# Mini-WaveGen.net
KiCad netlist of a schematic drawn in Altium Designer
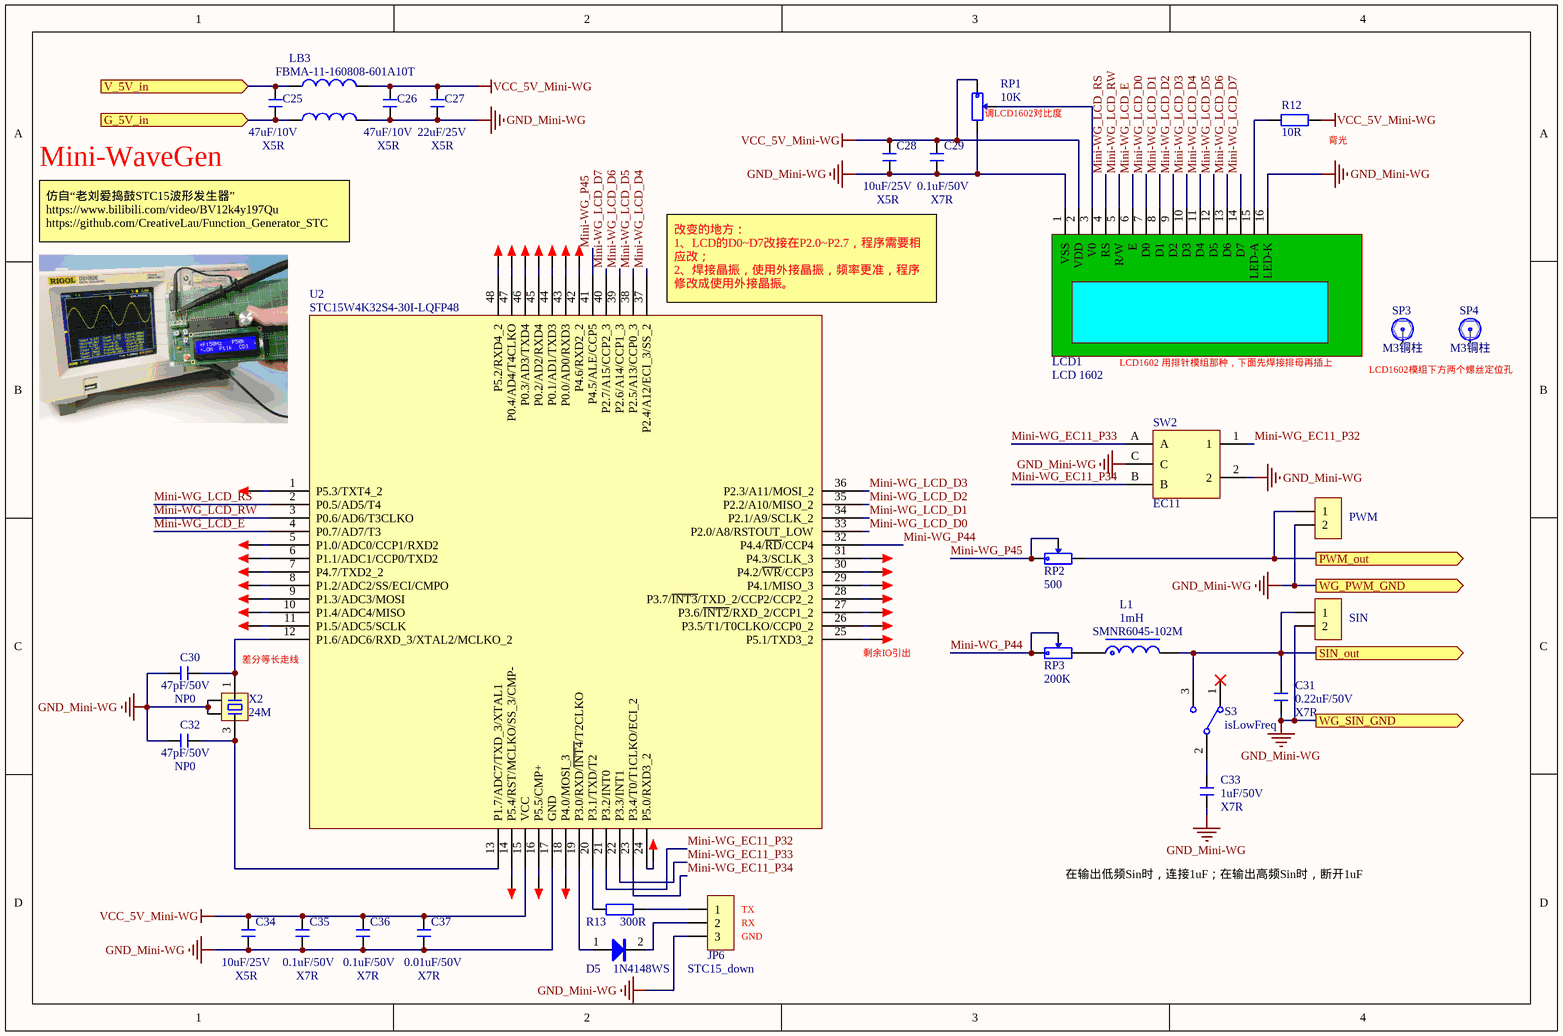
[diagram p0: Mini-WaveGen.SchDoc]

(export (version "E")
  (design (tool "Eeschema 10.0.6"))
  (components
    (comp (ref "C25")
      (value "47uF/10V")
      (footprint "C 1206_L")
      (description "无极性贴片电容 X5R")
      (fields (field (name "BOM名称") "X5R"))
      (libsource (lib "Foundation_temp") (part "C X5R"))
    )
    (comp (ref "C26")
      (value "47uF/10V")
      (footprint "C 1206_L")
      (description "无极性贴片电容 X5R")
      (fields (field (name "BOM名称") "X5R"))
      (libsource (lib "Foundation_temp") (part "C X5R"))
    )
    (comp (ref "C27")
      (value "22uF/25V")
      (footprint "C 0805_L")
      (description "无极性贴片电容 X5R")
      (fields (field (name "BOM名称") "X5R"))
      (libsource (lib "Foundation_temp") (part "C X5R"))
    )
    (comp (ref "C28")
      (value "10uF/25V")
      (footprint "C 0603_L")
      (description "无极性贴片电容 X5R")
      (fields (field (name "BOM名称") "X5R"))
      (libsource (lib "Foundation_temp") (part "C X5R"))
    )
    (comp (ref "C29")
      (value "0.1uF/50V")
      (footprint "C 0402_L")
      (description "无极性贴片电容 X7R")
      (fields (field (name "BOM名称") "X7R"))
      (libsource (lib "Foundation_temp") (part "C X7R"))
    )
    (comp (ref "C30")
      (value "47pF/50V")
      (footprint "C 0402_L")
      (description "无极性贴片电容 NP0")
      (fields (field (name "BOM名称") "NP0"))
      (libsource (lib "Foundation_temp") (part "C NP0"))
    )
    (comp (ref "C31")
      (value "0.22uF/50V")
      (footprint "C 0603_L")
      (description "无极性贴片电容 X7R")
      (fields (field (name "BOM名称") "X7R"))
      (libsource (lib "Foundation_temp") (part "C X7R"))
    )
    (comp (ref "C32")
      (value "47pF/50V")
      (footprint "C 0402_L")
      (description "无极性贴片电容 NP0")
      (fields (field (name "BOM名称") "NP0"))
      (libsource (lib "Foundation_temp") (part "C NP0"))
    )
    (comp (ref "C33")
      (value "1uF/50V")
      (footprint "C 0603_L")
      (description "无极性贴片电容 X7R")
      (fields (field (name "BOM名称") "X7R"))
      (libsource (lib "Foundation_temp") (part "C X7R"))
    )
    (comp (ref "C34")
      (value "10uF/25V")
      (footprint "C 0603_L")
      (description "无极性贴片电容 X5R")
      (fields (field (name "BOM名称") "X5R"))
      (libsource (lib "Foundation_temp") (part "C X5R"))
    )
    (comp (ref "C35")
      (value "0.1uF/50V")
      (footprint "C 0402_L")
      (description "无极性贴片电容 X7R")
      (fields (field (name "BOM名称") "X7R"))
      (libsource (lib "Foundation_temp") (part "C X7R"))
    )
    (comp (ref "C36")
      (value "0.1uF/50V")
      (footprint "C 0402_L")
      (description "无极性贴片电容 X7R")
      (fields (field (name "BOM名称") "X7R"))
      (libsource (lib "Foundation_temp") (part "C X7R"))
    )
    (comp (ref "C37")
      (value "0.01uF/50V")
      (footprint "C 0402_L")
      (description "无极性贴片电容 X7R")
      (fields (field (name "BOM名称") "X7R"))
      (libsource (lib "Foundation_temp") (part "C X7R"))
    )
    (comp (ref "D5")
      (value "1N4148WS")
      (footprint "SOD-323")
      (description "高速开关二极管")
      (fields (field (name "版权归属") "源创客"))
      (libsource (lib "8.1   - 二极管-整流桥") (part "1N4148"))
    )
    (comp (ref "JP4")
      (value "PWM")
      (footprint "HDR2.54-WS-2P")
      (description "2P接插件")
      (fields (field (name "版权归属") "源创客"))
      (libsource (lib "4.6   - 接插件-脚距2.54") (part "Header 2"))
    )
    (comp (ref "JP5")
      (value "SIN")
      (footprint "HDR2.54-WS-2P")
      (description "2P接插件")
      (fields (field (name "版权归属") "源创客"))
      (libsource (lib "4.6   - 接插件-脚距2.54") (part "Header 2"))
    )
    (comp (ref "JP6")
      (value "STC15_down")
      (footprint "HDR2.54-WS-3P")
      (description "3P接插件")
      (fields (field (name "版权归属") "源创客"))
      (libsource (lib "4.6   - 接插件-脚距2.54") (part "Header 3"))
    )
    (comp (ref "L1")
      (value "1mH")
      (footprint "NR6045")
      (description "SMNR6045-102M")
      (fields (field (name "BOM名称") "SMNR6045-102M") (field (name "版权归属") "源创客"))
      (libsource (lib "3.1   - 电阻-电容-电感") (part "L-NR"))
    )
    (comp (ref "LB3")
      (value "FBMA-11-160808-601A10T")
      (footprint "FB 0603_L")
      (description "磁珠 600R@100MHz")
      (fields (field (name "版权归属") "源创客"))
      (libsource (lib "3.1   - 电阻-电容-电感") (part "LB"))
    )
    (comp (ref "LB4")
      (value "FBMA-11-160808-601A10T")
      (footprint "FB 0603_L")
      (description "磁珠 600R@100MHz")
      (fields (field (name "版权归属") "源创客"))
      (libsource (lib "3.1   - 电阻-电容-电感") (part "LB"))
    )
    (comp (ref "LCD1")
      (value "LCD 1602")
      (footprint "LCD-1602")
      (fields (field (name "版权归属") "源创客"))
      (libsource (lib "9.2   - 显示器件") (part "LCD 1602"))
    )
    (comp (ref "R12")
      (value "10R")
      (footprint "R 0805_L")
      (description "贴片电阻 E-96 1%")
      (libsource (lib "Foundation_temp") (part "R"))
    )
    (comp (ref "R13")
      (value "300R")
      (footprint "R 0402_L")
      (description "贴片电阻 E-96 1%")
      (libsource (lib "Foundation_temp") (part "R"))
    )
    (comp (ref "RP1")
      (value "10K")
      (footprint "3362P")
      (description "插件单联电位器")
      (fields (field (name "版权归属") "源创客"))
      (libsource (lib "3.1   - 电阻-电容-电感") (part "RP-ID"))
    )
    (comp (ref "RP2")
      (value "500")
      (footprint "3362P")
      (description "插件单联电位器")
      (fields (field (name "版权归属") "源创客"))
      (libsource (lib "3.1   - 电阻-电容-电感") (part "RP-ID"))
    )
    (comp (ref "RP3")
      (value "200K")
      (footprint "3362P")
      (description "插件单联电位器")
      (fields (field (name "版权归属") "源创客"))
      (libsource (lib "3.1   - 电阻-电容-电感") (part "RP-ID"))
    )
    (comp (ref "S3")
      (value "isLowFreq")
      (footprint "MSK-12C01-07")
      (description "1路拨动开关")
      (fields (field (name "版权归属") "源创客"))
      (libsource (lib "5.1   - 按键-开关") (part "SSW-1P"))
    )
    (comp (ref "SP3")
      (value "M3铜柱")
      (footprint "M3x4_L")
      (description "铜柱")
      (fields (field (name "版权归属") "源创客"))
      (libsource (lib "15.1 - 未分类器件") (part "铜柱小焊盘"))
    )
    (comp (ref "SP4")
      (value "M3铜柱")
      (footprint "M3x4_L")
      (description "铜柱")
      (fields (field (name "版权归属") "源创客"))
      (libsource (lib "15.1 - 未分类器件") (part "铜柱小焊盘"))
    )
    (comp (ref "SW2")
      (value "EC11")
      (footprint "EC11-B")
      (description "数字开关编码器")
      (fields (field (name "版权归属") "源创客"))
      (libsource (lib "5.1   - 按键-开关") (part "EC11"))
    )
    (comp (ref "TP4")
      (value "IO")
      (footprint "TEST 1")
      (description "测试点")
      (fields (field (name "版权归属") "源创客"))
      (libsource (lib "15.1 - 未分类器件") (part "TEST"))
    )
    (comp (ref "TP5")
      (value "IO")
      (footprint "TEST 1")
      (description "测试点")
      (fields (field (name "版权归属") "源创客"))
      (libsource (lib "15.1 - 未分类器件") (part "TEST"))
    )
    (comp (ref "TP6")
      (value "IO")
      (footprint "TEST 1")
      (description "测试点")
      (fields (field (name "版权归属") "源创客"))
      (libsource (lib "15.1 - 未分类器件") (part "TEST"))
    )
    (comp (ref "TP7")
      (value "IO")
      (footprint "TEST 1")
      (description "测试点")
      (fields (field (name "版权归属") "源创客"))
      (libsource (lib "15.1 - 未分类器件") (part "TEST"))
    )
    (comp (ref "TP8")
      (value "IO")
      (footprint "TEST 1")
      (description "测试点")
      (fields (field (name "版权归属") "源创客"))
      (libsource (lib "15.1 - 未分类器件") (part "TEST"))
    )
    (comp (ref "TP9")
      (value "IO")
      (footprint "TEST 1")
      (description "测试点")
      (fields (field (name "版权归属") "源创客"))
      (libsource (lib "15.1 - 未分类器件") (part "TEST"))
    )
    (comp (ref "TP10")
      (value "IO")
      (footprint "TEST 1")
      (description "测试点")
      (fields (field (name "版权归属") "源创客"))
      (libsource (lib "15.1 - 未分类器件") (part "TEST"))
    )
    (comp (ref "TP11")
      (value "IO")
      (footprint "TEST 1")
      (description "测试点")
      (fields (field (name "版权归属") "源创客"))
      (libsource (lib "15.1 - 未分类器件") (part "TEST"))
    )
    (comp (ref "TP12")
      (value "IO")
      (footprint "TEST 1")
      (description "测试点")
      (fields (field (name "版权归属") "源创客"))
      (libsource (lib "15.1 - 未分类器件") (part "TEST"))
    )
    (comp (ref "TP13")
      (value "IO")
      (footprint "TEST 1")
      (description "测试点")
      (fields (field (name "版权归属") "源创客"))
      (libsource (lib "15.1 - 未分类器件") (part "TEST"))
    )
    (comp (ref "TP14")
      (value "IO")
      (footprint "TEST 1")
      (description "测试点")
      (fields (field (name "版权归属") "源创客"))
      (libsource (lib "15.1 - 未分类器件") (part "TEST"))
    )
    (comp (ref "TP15")
      (value "IO")
      (footprint "TEST 1")
      (description "测试点")
      (fields (field (name "版权归属") "源创客"))
      (libsource (lib "15.1 - 未分类器件") (part "TEST"))
    )
    (comp (ref "TP16")
      (value "IO")
      (footprint "TEST 1")
      (description "测试点")
      (fields (field (name "版权归属") "源创客"))
      (libsource (lib "15.1 - 未分类器件") (part "TEST"))
    )
    (comp (ref "TP17")
      (value "IO")
      (footprint "TEST 1")
      (description "测试点")
      (fields (field (name "版权归属") "源创客"))
      (libsource (lib "15.1 - 未分类器件") (part "TEST"))
    )
    (comp (ref "TP18")
      (value "IO")
      (footprint "TEST 1")
      (description "测试点")
      (fields (field (name "版权归属") "源创客"))
      (libsource (lib "15.1 - 未分类器件") (part "TEST"))
    )
    (comp (ref "TP19")
      (value "IO")
      (footprint "TEST 1")
      (description "测试点")
      (fields (field (name "版权归属") "源创客"))
      (libsource (lib "15.1 - 未分类器件") (part "TEST"))
    )
    (comp (ref "TP20")
      (value "IO")
      (footprint "TEST 1")
      (description "测试点")
      (fields (field (name "版权归属") "源创客"))
      (libsource (lib "15.1 - 未分类器件") (part "TEST"))
    )
    (comp (ref "TP21")
      (value "IO")
      (footprint "TEST 1")
      (description "测试点")
      (fields (field (name "版权归属") "源创客"))
      (libsource (lib "15.1 - 未分类器件") (part "TEST"))
    )
    (comp (ref "TP22")
      (value "IO")
      (footprint "TEST 1")
      (description "测试点")
      (fields (field (name "版权归属") "源创客"))
      (libsource (lib "15.1 - 未分类器件") (part "TEST"))
    )
    (comp (ref "TP23")
      (value "IO")
      (footprint "TEST 1")
      (description "测试点")
      (fields (field (name "版权归属") "源创客"))
      (libsource (lib "15.1 - 未分类器件") (part "TEST"))
    )
    (comp (ref "TP24")
      (value "IO")
      (footprint "TEST 1")
      (description "测试点")
      (fields (field (name "版权归属") "源创客"))
      (libsource (lib "15.1 - 未分类器件") (part "TEST"))
    )
    (comp (ref "TP25")
      (value "IO")
      (footprint "TEST 1")
      (description "测试点")
      (fields (field (name "版权归属") "源创客"))
      (libsource (lib "15.1 - 未分类器件") (part "TEST"))
    )
    (comp (ref "TP26")
      (value "IO")
      (footprint "TEST 1")
      (description "测试点")
      (fields (field (name "版权归属") "源创客"))
      (libsource (lib "15.1 - 未分类器件") (part "TEST"))
    )
    (comp (ref "TP27")
      (value "IO")
      (footprint "TEST 1")
      (description "测试点")
      (fields (field (name "版权归属") "源创客"))
      (libsource (lib "15.1 - 未分类器件") (part "TEST"))
    )
    (comp (ref "TP28")
      (value "IO")
      (footprint "TEST 1")
      (description "测试点")
      (fields (field (name "版权归属") "源创客"))
      (libsource (lib "15.1 - 未分类器件") (part "TEST"))
    )
    (comp (ref "TP29")
      (value "IO")
      (footprint "TEST 1")
      (description "测试点")
      (fields (field (name "版权归属") "源创客"))
      (libsource (lib "15.1 - 未分类器件") (part "TEST"))
    )
    (comp (ref "U2")
      (value "STC15W4K32S4-30I-LQFP48")
      (footprint "LQFP48")
      (libsource (lib "stcmcu_altium20.1.10") (part "STC15W4K60S4_LQFP48"))
    )
    (comp (ref "X2")
      (value "24M")
      (footprint "OSC 3225-4P")
      (description "4脚无源晶振")
      (fields (field (name "版权归属") "源创客"))
      (libsource (lib "10.1 - 保险丝-晶振") (part "XTAL-4P"))
    )
  )
  (nets
    (net (code "1") (name "/G_5V_in") (class "Default")
      (node (ref "C25") (pin "1") (pinfunction "1_1") (pintype "passive"))
      (node (ref "LB4") (pin "1") (pinfunction "1_1") (pintype "passive"))
    )
    (net (code "2") (name "/Mini-WG_EC11_P32") (class "Default")
      (node (ref "SW2") (pin "1") (pinfunction "1_1") (pintype "passive"))
      (node (ref "U2") (pin "21") (pinfunction "P3.2/INT0_21") (pintype "passive"))
    )
    (net (code "3") (name "/Mini-WG_EC11_P33") (class "Default")
      (node (ref "SW2") (pin "A") (pinfunction "A_A") (pintype "passive"))
      (node (ref "U2") (pin "22") (pinfunction "P3.3/INT1_22") (pintype "passive"))
    )
    (net (code "4") (name "/Mini-WG_EC11_P34") (class "Default")
      (node (ref "SW2") (pin "B") (pinfunction "B_B") (pintype "passive"))
      (node (ref "U2") (pin "23") (pinfunction "P3.4/T0/T1CLKO/ECI_2_23") (pintype "passive"))
    )
    (net (code "5") (name "/Mini-WG_LCD_D0") (class "Default")
      (node (ref "LCD1") (pin "7") (pinfunction "D0_7") (pintype "passive"))
      (node (ref "U2") (pin "33") (pinfunction "P2.0/A8/RSTOUT_LOW_33") (pintype "passive"))
    )
    (net (code "6") (name "/Mini-WG_LCD_D1") (class "Default")
      (node (ref "LCD1") (pin "8") (pinfunction "D1_8") (pintype "passive"))
      (node (ref "U2") (pin "34") (pinfunction "P2.1/A9/SCLK_2_34") (pintype "passive"))
    )
    (net (code "7") (name "/Mini-WG_LCD_D2") (class "Default")
      (node (ref "LCD1") (pin "9") (pinfunction "D2_9") (pintype "passive"))
      (node (ref "U2") (pin "35") (pinfunction "P2.2/A10/MISO_2_35") (pintype "passive"))
    )
    (net (code "8") (name "/Mini-WG_LCD_D3") (class "Default")
      (node (ref "LCD1") (pin "10") (pinfunction "D3_10") (pintype "passive"))
      (node (ref "U2") (pin "36") (pinfunction "P2.3/A11/MOSI_2_36") (pintype "passive"))
    )
    (net (code "9") (name "/Mini-WG_LCD_D4") (class "Default")
      (node (ref "LCD1") (pin "11") (pinfunction "D4_11") (pintype "passive"))
      (node (ref "U2") (pin "37") (pinfunction "P2.4/A12/ECI_3/SS_2_37") (pintype "passive"))
    )
    (net (code "10") (name "/Mini-WG_LCD_D5") (class "Default")
      (node (ref "LCD1") (pin "12") (pinfunction "D5_12") (pintype "passive"))
      (node (ref "U2") (pin "38") (pinfunction "P2.5/A13/CCP0_3_38") (pintype "passive"))
    )
    (net (code "11") (name "/Mini-WG_LCD_D6") (class "Default")
      (node (ref "LCD1") (pin "13") (pinfunction "D6_13") (pintype "passive"))
      (node (ref "U2") (pin "39") (pinfunction "P2.6/A14/CCP1_3_39") (pintype "passive"))
    )
    (net (code "12") (name "/Mini-WG_LCD_D7") (class "Default")
      (node (ref "LCD1") (pin "14") (pinfunction "D7_14") (pintype "passive"))
      (node (ref "U2") (pin "40") (pinfunction "P2.7/A15/CCP2_3_40") (pintype "passive"))
    )
    (net (code "13") (name "/Mini-WG_LCD_E") (class "Default")
      (node (ref "LCD1") (pin "6") (pinfunction "E_6") (pintype "passive"))
      (node (ref "U2") (pin "4") (pinfunction "P0.7/AD7/T3_4") (pintype "passive"))
    )
    (net (code "14") (name "/Mini-WG_LCD_RS") (class "Default")
      (node (ref "LCD1") (pin "4") (pinfunction "RS_4") (pintype "passive"))
      (node (ref "U2") (pin "2") (pinfunction "P0.5/AD5/T4_2") (pintype "passive"))
    )
    (net (code "15") (name "/Mini-WG_LCD_RW") (class "Default")
      (node (ref "LCD1") (pin "5") (pinfunction "R/W_5") (pintype "passive"))
      (node (ref "U2") (pin "3") (pinfunction "P0.6/AD6/T3CLKO_3") (pintype "passive"))
    )
    (net (code "16") (name "/Mini-WG_P44") (class "Default")
      (node (ref "RP3") (pin "1") (pinfunction "1_1") (pintype "passive"))
      (node (ref "RP3") (pin "2") (pinfunction "2_2") (pintype "passive"))
      (node (ref "U2") (pin "32") (pinfunction "P4.4/~{RD}/CCP4_32") (pintype "passive"))
    )
    (net (code "17") (name "/Mini-WG_P45") (class "Default")
      (node (ref "RP2") (pin "1") (pinfunction "1_1") (pintype "passive"))
      (node (ref "RP2") (pin "2") (pinfunction "2_2") (pintype "passive"))
      (node (ref "U2") (pin "41") (pinfunction "P4.5/ALE/CCP5_41") (pintype "passive"))
    )
    (net (code "18") (name "/PWM_out") (class "Default")
      (node (ref "JP4") (pin "1") (pinfunction "1_1") (pintype "passive"))
      (node (ref "RP2") (pin "3") (pinfunction "3_3") (pintype "passive"))
    )
    (net (code "19") (name "/SIN_out") (class "Default")
      (node (ref "C31") (pin "1") (pinfunction "1_1") (pintype "passive"))
      (node (ref "JP5") (pin "1") (pinfunction "1_1") (pintype "passive"))
      (node (ref "L1") (pin "2") (pinfunction "2_2") (pintype "passive"))
      (node (ref "S3") (pin "3") (pinfunction "3_3") (pintype "passive"))
    )
    (net (code "20") (name "/V_5V_in") (class "Default")
      (node (ref "C25") (pin "2") (pinfunction "2_2") (pintype "passive"))
      (node (ref "LB3") (pin "1") (pinfunction "1_1") (pintype "passive"))
    )
    (net (code "21") (name "GND_Mini-WG") (class "Default")
      (node (ref "C26") (pin "1") (pinfunction "1_1") (pintype "passive"))
      (node (ref "C27") (pin "1") (pinfunction "1_1") (pintype "passive"))
      (node (ref "C28") (pin "1") (pinfunction "1_1") (pintype "passive"))
      (node (ref "C29") (pin "2") (pinfunction "2_2") (pintype "passive"))
      (node (ref "C30") (pin "2") (pinfunction "2_2") (pintype "passive"))
      (node (ref "C31") (pin "2") (pinfunction "2_2") (pintype "passive"))
      (node (ref "C32") (pin "2") (pinfunction "2_2") (pintype "passive"))
      (node (ref "C33") (pin "1") (pinfunction "1_1") (pintype "passive"))
      (node (ref "C34") (pin "1") (pinfunction "1_1") (pintype "passive"))
      (node (ref "C35") (pin "2") (pinfunction "2_2") (pintype "passive"))
      (node (ref "C36") (pin "2") (pinfunction "2_2") (pintype "passive"))
      (node (ref "C37") (pin "2") (pinfunction "2_2") (pintype "passive"))
      (node (ref "JP4") (pin "2") (pinfunction "2_2") (pintype "passive"))
      (node (ref "JP5") (pin "2") (pinfunction "2_2") (pintype "passive"))
      (node (ref "JP6") (pin "3") (pinfunction "3_3") (pintype "passive"))
      (node (ref "LB4") (pin "2") (pinfunction "2_2") (pintype "passive"))
      (node (ref "LCD1") (pin "1") (pinfunction "VSS_1") (pintype "passive"))
      (node (ref "LCD1") (pin "16") (pinfunction "LED-K_16") (pintype "passive"))
      (node (ref "RP1") (pin "3") (pinfunction "3_3") (pintype "passive"))
      (node (ref "SW2") (pin "2") (pinfunction "2_2") (pintype "passive"))
      (node (ref "SW2") (pin "C") (pinfunction "C_C") (pintype "passive"))
      (node (ref "U2") (pin "17") (pinfunction "GND_17") (pintype "passive"))
      (node (ref "X2") (pin "2") (pinfunction "2_2") (pintype "passive"))
      (node (ref "X2") (pin "4") (pinfunction "4_4") (pintype "passive"))
    )
    (net (code "22") (name "Net-(C33-Pad2)") (class "Default")
      (node (ref "C33") (pin "2") (pinfunction "2_2") (pintype "passive"))
      (node (ref "S3") (pin "2") (pinfunction "2_2") (pintype "passive"))
    )
    (net (code "23") (name "Net-(D5-A)") (class "Default")
      (node (ref "D5") (pin "1") (pinfunction "A_1") (pintype "passive"))
      (node (ref "U2") (pin "19") (pinfunction "P3.0/RXD/~{INT4}/T2CLKO_19") (pintype "passive"))
    )
    (net (code "24") (name "Net-(D5-K)") (class "Default")
      (node (ref "D5") (pin "2") (pinfunction "K_2") (pintype "passive"))
      (node (ref "JP6") (pin "2") (pinfunction "2_2") (pintype "passive"))
    )
    (net (code "25") (name "Net-(JP6-Pad1)") (class "Default")
      (node (ref "JP6") (pin "1") (pinfunction "1_1") (pintype "passive"))
      (node (ref "R13") (pin "1") (pinfunction "1_1") (pintype "passive"))
    )
    (net (code "26") (name "Net-(L1-Pad1)") (class "Default")
      (node (ref "L1") (pin "1") (pinfunction "1_1") (pintype "passive"))
      (node (ref "RP3") (pin "3") (pinfunction "3_3") (pintype "passive"))
    )
    (net (code "27") (name "Net-(LCD1-LED-A)") (class "Default")
      (node (ref "LCD1") (pin "15") (pinfunction "LED-A_15") (pintype "passive"))
      (node (ref "R12") (pin "2") (pinfunction "2_2") (pintype "passive"))
    )
    (net (code "28") (name "Net-(LCD1-V0)") (class "Default")
      (node (ref "LCD1") (pin "3") (pinfunction "V0_3") (pintype "passive"))
      (node (ref "RP1") (pin "2") (pinfunction "2_2") (pintype "passive"))
    )
    (net (code "29") (name "Net-(U2-P0.0{slash}AD0{slash}RXD3)") (class "Default")
      (node (ref "TP9") (pin "1") (pinfunction "1_1") (pintype "passive"))
      (node (ref "U2") (pin "43") (pinfunction "P0.0/AD0/RXD3_43") (pintype "passive"))
    )
    (net (code "30") (name "Net-(U2-P0.1{slash}AD1{slash}TXD3)") (class "Default")
      (node (ref "TP8") (pin "1") (pinfunction "1_1") (pintype "passive"))
      (node (ref "U2") (pin "44") (pinfunction "P0.1/AD1/TXD3_44") (pintype "passive"))
    )
    (net (code "31") (name "Net-(U2-P0.2{slash}AD2{slash}RXD4)") (class "Default")
      (node (ref "TP7") (pin "1") (pinfunction "1_1") (pintype "passive"))
      (node (ref "U2") (pin "45") (pinfunction "P0.2/AD2/RXD4_45") (pintype "passive"))
    )
    (net (code "32") (name "Net-(U2-P0.3{slash}AD3{slash}TXD4)") (class "Default")
      (node (ref "TP6") (pin "1") (pinfunction "1_1") (pintype "passive"))
      (node (ref "U2") (pin "46") (pinfunction "P0.3/AD3/TXD4_46") (pintype "passive"))
    )
    (net (code "33") (name "Net-(U2-P0.4{slash}AD4{slash}T4CLKO)") (class "Default")
      (node (ref "TP5") (pin "1") (pinfunction "1_1") (pintype "passive"))
      (node (ref "U2") (pin "47") (pinfunction "P0.4/AD4/T4CLKO_47") (pintype "passive"))
    )
    (net (code "34") (name "Net-(U2-P1.0{slash}ADC0{slash}CCP1{slash}RXD2)") (class "Default")
      (node (ref "TP13") (pin "1") (pinfunction "1_1") (pintype "passive"))
      (node (ref "U2") (pin "5") (pinfunction "P1.0/ADC0/CCP1/RXD2_5") (pintype "passive"))
    )
    (net (code "35") (name "Net-(U2-P1.1{slash}ADC1{slash}CCP0{slash}TXD2)") (class "Default")
      (node (ref "TP15") (pin "1") (pinfunction "1_1") (pintype "passive"))
      (node (ref "U2") (pin "6") (pinfunction "P1.1/ADC1/CCP0/TXD2_6") (pintype "passive"))
    )
    (net (code "36") (name "Net-(U2-P1.2{slash}ADC2{slash}SS{slash}ECI{slash}CMPO)") (class "Default")
      (node (ref "TP19") (pin "1") (pinfunction "1_1") (pintype "passive"))
      (node (ref "U2") (pin "8") (pinfunction "P1.2/ADC2/SS/ECI/CMPO_8") (pintype "passive"))
    )
    (net (code "37") (name "Net-(U2-P1.3{slash}ADC3{slash}MOSI)") (class "Default")
      (node (ref "TP21") (pin "1") (pinfunction "1_1") (pintype "passive"))
      (node (ref "U2") (pin "9") (pinfunction "P1.3/ADC3/MOSI_9") (pintype "passive"))
    )
    (net (code "38") (name "Net-(U2-P1.4{slash}ADC4{slash}MISO)") (class "Default")
      (node (ref "TP23") (pin "1") (pinfunction "1_1") (pintype "passive"))
      (node (ref "U2") (pin "10") (pinfunction "P1.4/ADC4/MISO_10") (pintype "passive"))
    )
    (net (code "39") (name "Net-(U2-P1.5{slash}ADC5{slash}SCLK)") (class "Default")
      (node (ref "TP25") (pin "1") (pinfunction "1_1") (pintype "passive"))
      (node (ref "U2") (pin "11") (pinfunction "P1.5/ADC5/SCLK_11") (pintype "passive"))
    )
    (net (code "40") (name "Net-(U2-P1.6{slash}ADC6{slash}RXD_3{slash}XTAL2{slash}MCLKO_2)") (class "Default")
      (node (ref "C30") (pin "1") (pinfunction "1_1") (pintype "passive"))
      (node (ref "U2") (pin "12") (pinfunction "P1.6/ADC6/RXD_3/XTAL2/MCLKO_2_12") (pintype "passive"))
      (node (ref "X2") (pin "1") (pinfunction "1_1") (pintype "passive"))
    )
    (net (code "41") (name "Net-(U2-P1.7{slash}ADC7{slash}TXD_3{slash}XTAL1)") (class "Default")
      (node (ref "C32") (pin "1") (pinfunction "1_1") (pintype "passive"))
      (node (ref "U2") (pin "13") (pinfunction "P1.7/ADC7/TXD_3/XTAL1_13") (pintype "passive"))
      (node (ref "X2") (pin "3") (pinfunction "3_3") (pintype "passive"))
    )
    (net (code "42") (name "Net-(U2-P3.1{slash}TXD{slash}T2)") (class "Default")
      (node (ref "R13") (pin "2") (pinfunction "2_2") (pintype "passive"))
      (node (ref "U2") (pin "20") (pinfunction "P3.1/TXD/T2_20") (pintype "passive"))
    )
    (net (code "43") (name "Net-(U2-P3.5{slash}T1{slash}T0CLKO{slash}CCP0_2)") (class "Default")
      (node (ref "TP22") (pin "1") (pinfunction "1_1") (pintype "passive"))
      (node (ref "U2") (pin "26") (pinfunction "P3.5/T1/T0CLKO/CCP0_2_26") (pintype "passive"))
    )
    (net (code "44") (name "Net-(U2-P3.6{slash}~{INT2}{slash}RXD_2{slash}CCP1_2)") (class "Default")
      (node (ref "TP20") (pin "1") (pinfunction "1_1") (pintype "passive"))
      (node (ref "U2") (pin "27") (pinfunction "P3.6/~{INT2}/RXD_2/CCP1_2_27") (pintype "passive"))
    )
    (net (code "45") (name "Net-(U2-P3.7{slash}~{INT3}{slash}TXD_2{slash}CCP2{slash}CCP2_2)") (class "Default")
      (node (ref "TP18") (pin "1") (pinfunction "1_1") (pintype "passive"))
      (node (ref "U2") (pin "28") (pinfunction "P3.7/~{INT3}/TXD_2/CCP2/CCP2_2_28") (pintype "passive"))
    )
    (net (code "46") (name "Net-(U2-P4.0{slash}MOSI_3)") (class "Default")
      (node (ref "TP29") (pin "1") (pinfunction "1_1") (pintype "passive"))
      (node (ref "U2") (pin "18") (pinfunction "P4.0/MOSI_3_18") (pintype "passive"))
    )
    (net (code "47") (name "Net-(U2-P4.1{slash}MISO_3)") (class "Default")
      (node (ref "TP16") (pin "1") (pinfunction "1_1") (pintype "passive"))
      (node (ref "U2") (pin "29") (pinfunction "P4.1/MISO_3_29") (pintype "passive"))
    )
    (net (code "48") (name "Net-(U2-P4.2{slash}~{WR}{slash}CCP3)") (class "Default")
      (node (ref "TP14") (pin "1") (pinfunction "1_1") (pintype "passive"))
      (node (ref "U2") (pin "30") (pinfunction "P4.2/~{WR}/CCP3_30") (pintype "passive"))
    )
    (net (code "49") (name "Net-(U2-P4.3{slash}SCLK_3)") (class "Default")
      (node (ref "TP12") (pin "1") (pinfunction "1_1") (pintype "passive"))
      (node (ref "U2") (pin "31") (pinfunction "P4.3/SCLK_3_31") (pintype "passive"))
    )
    (net (code "50") (name "Net-(U2-P4.6{slash}RXD2_2)") (class "Default")
      (node (ref "TP10") (pin "1") (pinfunction "1_1") (pintype "passive"))
      (node (ref "U2") (pin "42") (pinfunction "P4.6/RXD2_2_42") (pintype "passive"))
    )
    (net (code "51") (name "Net-(U2-P4.7{slash}TXD2_2)") (class "Default")
      (node (ref "TP17") (pin "1") (pinfunction "1_1") (pintype "passive"))
      (node (ref "U2") (pin "7") (pinfunction "P4.7/TXD2_2_7") (pintype "passive"))
    )
    (net (code "52") (name "Net-(U2-P5.0{slash}RXD3_2)") (class "Default")
      (node (ref "TP26") (pin "1") (pinfunction "1_1") (pintype "passive"))
      (node (ref "U2") (pin "24") (pinfunction "P5.0/RXD3_2_24") (pintype "passive"))
    )
    (net (code "53") (name "Net-(U2-P5.1{slash}TXD3_2)") (class "Default")
      (node (ref "TP24") (pin "1") (pinfunction "1_1") (pintype "passive"))
      (node (ref "U2") (pin "25") (pinfunction "P5.1/TXD3_2_25") (pintype "passive"))
    )
    (net (code "54") (name "Net-(U2-P5.2{slash}RXD4_2)") (class "Default")
      (node (ref "TP4") (pin "1") (pinfunction "1_1") (pintype "passive"))
      (node (ref "U2") (pin "48") (pinfunction "P5.2/RXD4_2_48") (pintype "passive"))
    )
    (net (code "55") (name "Net-(U2-P5.3{slash}TXT4_2)") (class "Default")
      (node (ref "TP11") (pin "1") (pinfunction "1_1") (pintype "passive"))
      (node (ref "U2") (pin "1") (pinfunction "P5.3/TXT4_2_1") (pintype "passive"))
    )
    (net (code "56") (name "Net-(U2-P5.4{slash}RST{slash}MCLKO{slash}SS_3{slash}CMP-)") (class "Default")
      (node (ref "TP27") (pin "1") (pinfunction "1_1") (pintype "passive"))
      (node (ref "U2") (pin "14") (pinfunction "P5.4/RST/MCLKO/SS_3/CMP-_14") (pintype "passive"))
    )
    (net (code "57") (name "Net-(U2-P5.5{slash}CMP+)") (class "Default")
      (node (ref "TP28") (pin "1") (pinfunction "1_1") (pintype "passive"))
      (node (ref "U2") (pin "16") (pinfunction "P5.5/CMP+_16") (pintype "passive"))
    )
    (net (code "58") (name "VCC_5V_Mini-WG") (class "Default")
      (node (ref "C26") (pin "2") (pinfunction "2_2") (pintype "passive"))
      (node (ref "C27") (pin "2") (pinfunction "2_2") (pintype "passive"))
      (node (ref "C28") (pin "2") (pinfunction "2_2") (pintype "passive"))
      (node (ref "C29") (pin "1") (pinfunction "1_1") (pintype "passive"))
      (node (ref "C34") (pin "2") (pinfunction "2_2") (pintype "passive"))
      (node (ref "C35") (pin "1") (pinfunction "1_1") (pintype "passive"))
      (node (ref "C36") (pin "1") (pinfunction "1_1") (pintype "passive"))
      (node (ref "C37") (pin "1") (pinfunction "1_1") (pintype "passive"))
      (node (ref "LB3") (pin "2") (pinfunction "2_2") (pintype "passive"))
      (node (ref "LCD1") (pin "2") (pinfunction "VDD_2") (pintype "passive"))
      (node (ref "R12") (pin "1") (pinfunction "1_1") (pintype "passive"))
      (node (ref "RP1") (pin "1") (pinfunction "1_1") (pintype "passive"))
      (node (ref "U2") (pin "15") (pinfunction "VCC_15") (pintype "passive"))
    )
    (net (code "59") (name "unconnected-(S3-Pad1)") (class "Default")
      (node (ref "S3") (pin "1") (pinfunction "1_1") (pintype "passive+no_connect"))
    )
    (net (code "60") (name "unconnected-(SP3-Pad1)") (class "Default")
      (node (ref "SP3") (pin "1") (pinfunction "1_1") (pintype "passive"))
    )
    (net (code "61") (name "unconnected-(SP4-Pad1)") (class "Default")
      (node (ref "SP4") (pin "1") (pinfunction "1_1") (pintype "passive"))
    )
  )
)
